# WATCHDOG.net
KiCad netlist of a schematic drawn in Altium Designer
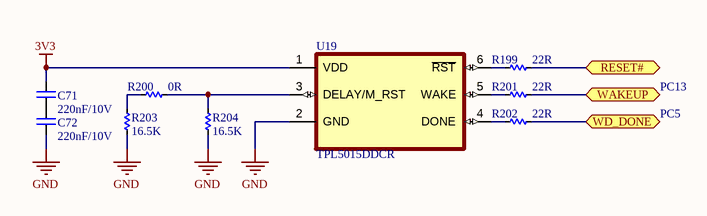
[diagram p0: WATCHDOG.SchDoc]

(export (version "E")
  (design (tool "Eeschema 10.0.6"))
  (components
    (comp (ref "C71")
      (value "220nF/10V")
      (footprint "CAP_C_1608X80")
      (description "CAP_Chip")
      (libsource (lib "LABLIB") (part "CAP_SMD"))
    )
    (comp (ref "C72")
      (value "220nF/10V")
      (footprint "CAP_C_1608X80")
      (description "CAP_Chip")
      (libsource (lib "LABLIB") (part "CAP_SMD"))
    )
    (comp (ref "R199")
      (value "22R")
      (footprint "RES_C_1608X60")
      (description "RES")
      (libsource (lib "LABLIB") (part "_RES_B_2"))
    )
    (comp (ref "R200")
      (value "0R")
      (footprint "RES_C_1608X60")
      (description "RES")
      (libsource (lib "LABLIB") (part "_RES_B_2"))
    )
    (comp (ref "R201")
      (value "22R")
      (footprint "RES_C_1608X60")
      (description "RES")
      (libsource (lib "LABLIB") (part "_RES_B_2"))
    )
    (comp (ref "R202")
      (value "22R")
      (footprint "RES_C_1608X60")
      (description "RES")
      (libsource (lib "LABLIB") (part "_RES_B_2"))
    )
    (comp (ref "R203")
      (value "16.5K")
      (footprint "RES_C_1608X60")
      (description "RES")
      (libsource (lib "LABLIB") (part "_RES_B_2"))
    )
    (comp (ref "R204")
      (value "16.5K")
      (footprint "RES_C_1608X60")
      (description "RES")
      (libsource (lib "LABLIB") (part "_RES_B_2"))
    )
    (comp (ref "U19")
      (value "TPL5015DDCR")
      (footprint "TPL5010DDCR")
      (description "OSC PROG TIMER TSOT23-6")
      (libsource (lib "COMM_SCHLIB") (part "TPL5015DDCR"))
    )
  )
  (nets
    (net (code "1") (name "/RESET#") (class "Default")
      (node (ref "R199") (pin "2") (pinfunction "2_2") (pintype "passive"))
    )
    (net (code "2") (name "/WAKEUP") (class "Default")
      (node (ref "R201") (pin "2") (pinfunction "2_2") (pintype "passive"))
    )
    (net (code "3") (name "/WD_DONE") (class "Default")
      (node (ref "R202") (pin "2") (pinfunction "2_2") (pintype "passive"))
    )
    (net (code "4") (name "3V3") (class "Default")
      (node (ref "C71") (pin "2") (pinfunction "2_2") (pintype "passive"))
      (node (ref "U19") (pin "1") (pinfunction "VDD_1") (pintype "power_in"))
    )
    (net (code "5") (name "GND") (class "Default")
      (node (ref "C72") (pin "1") (pinfunction "1_1") (pintype "passive"))
      (node (ref "R203") (pin "1") (pinfunction "1_1") (pintype "passive"))
      (node (ref "R204") (pin "1") (pinfunction "1_1") (pintype "passive"))
      (node (ref "U19") (pin "2") (pinfunction "GND_2") (pintype "power_in"))
    )
    (net (code "6") (name "Net-(C71-Pad1)") (class "Default")
      (node (ref "C71") (pin "1") (pinfunction "1_1") (pintype "passive"))
      (node (ref "C72") (pin "2") (pinfunction "2_2") (pintype "passive"))
    )
    (net (code "7") (name "Net-(R200-Pad1)") (class "Default")
      (node (ref "R200") (pin "1") (pinfunction "1_1") (pintype "passive"))
      (node (ref "R203") (pin "2") (pinfunction "2_2") (pintype "passive"))
    )
    (net (code "8") (name "Net-(U19-DELAY{slash}M_RST)") (class "Default")
      (node (ref "R200") (pin "2") (pinfunction "2_2") (pintype "passive"))
      (node (ref "R204") (pin "2") (pinfunction "2_2") (pintype "passive"))
      (node (ref "U19") (pin "3") (pinfunction "DELAY/M_RST_3") (pintype "bidirectional"))
    )
    (net (code "9") (name "Net-(U19-DONE)") (class "Default")
      (node (ref "R202") (pin "1") (pinfunction "1_1") (pintype "passive"))
      (node (ref "U19") (pin "4") (pinfunction "DONE_4") (pintype "bidirectional"))
    )
    (net (code "10") (name "Net-(U19-WAKE)") (class "Default")
      (node (ref "R201") (pin "1") (pinfunction "1_1") (pintype "passive"))
      (node (ref "U19") (pin "5") (pinfunction "WAKE_5") (pintype "bidirectional"))
    )
    (net (code "11") (name "Net-(U19-~{RST})") (class "Default")
      (node (ref "R199") (pin "1") (pinfunction "1_1") (pintype "passive"))
      (node (ref "U19") (pin "6") (pinfunction "~{RST}_6") (pintype "bidirectional"))
    )
  )
)
